# 0.net
KiCad netlist of a schematic drawn in Altium Designer
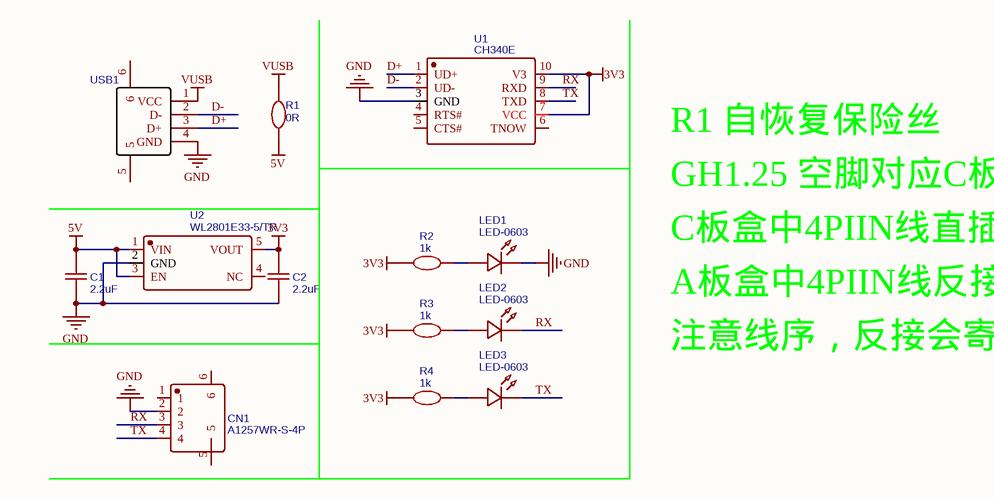
[diagram p0: 0.SchDoc]

(export (version "E")
  (design (tool "Eeschema 10.0.6"))
  (components
    (comp (ref "C1")
      (value "2.2uF")
      (footprint "C0603")
      (fields (field (name "CONTRIBUTOR") "LCEDA_Lib"))
      (libsource (lib "altium-import") (part "root_3_0.1u_"))
    )
    (comp (ref "C2")
      (value "2.2uF")
      (footprint "C0603")
      (fields (field (name "CONTRIBUTOR") "LCEDA_Lib"))
      (libsource (lib "altium-import") (part "root_3_0.1u_"))
    )
    (comp (ref "CN1")
      (value "A1257WR-S-4P")
      (footprint "CONN-SMD_A1257WR-S-4P")
      (fields (field (name "BOM_SUPPLIER PART") "C225127") (field (name "CONTRIBUTOR") "LCSC"))
      (libsource (lib "altium-import") (part "root_0_A1257WR-S-4P_"))
    )
    (comp (ref "LED1")
      (value "LED-0603")
      (footprint "LED0603_RED")
      (fields
        (field (name "BOM_MANUFACTURER PART") "19-217/R6C-AL1M2VY/3T")
        (field (name "BOM_SUPPLIER PART") "C72044")
        (field (name "CONTRIBUTOR") "LCEDA_01")
      )
      (libsource (lib "altium-import") (part "root_0_LED-0603_R_"))
    )
    (comp (ref "LED2")
      (value "LED-0603")
      (footprint "LED0603_RED")
      (fields
        (field (name "BOM_MANUFACTURER PART") "19-217/R6C-AL1M2VY/3T")
        (field (name "BOM_SUPPLIER PART") "C72044")
        (field (name "CONTRIBUTOR") "LCEDA_01")
      )
      (libsource (lib "altium-import") (part "root_0_LED-0603_R_"))
    )
    (comp (ref "LED3")
      (value "LED-0603")
      (footprint "LED0603_RED")
      (fields
        (field (name "BOM_MANUFACTURER PART") "19-217/R6C-AL1M2VY/3T")
        (field (name "BOM_SUPPLIER PART") "C72044")
        (field (name "CONTRIBUTOR") "LCEDA_01")
      )
      (libsource (lib "altium-import") (part "root_0_LED-0603_R_"))
    )
    (comp (ref "R1")
      (value "0R")
      (footprint "R0603")
      (fields (field (name "CONTRIBUTOR") "LCEDA_Lib"))
      (libsource (lib "altium-import") (part "root_3_1k_"))
    )
    (comp (ref "R2")
      (value "1k")
      (footprint "R0603")
      (fields (field (name "CONTRIBUTOR") "LCEDA_Lib"))
      (libsource (lib "altium-import") (part "root_0_1k_"))
    )
    (comp (ref "R3")
      (value "1k")
      (footprint "R0603")
      (fields (field (name "CONTRIBUTOR") "LCEDA_Lib"))
      (libsource (lib "altium-import") (part "root_0_1k_"))
    )
    (comp (ref "R4")
      (value "1k")
      (footprint "R0603")
      (fields (field (name "CONTRIBUTOR") "LCEDA_Lib"))
      (libsource (lib "altium-import") (part "root_0_1k_"))
    )
    (comp (ref "U1")
      (value "CH340E")
      (footprint "MSOP-10_L3.0-W3.0-P0.50-LS5.0-BL")
      (fields (field (name "BOM_SUPPLIER PART") "C99652"))
      (libsource (lib "altium-import") (part "root_0_CH340E_"))
    )
    (comp (ref "U2")
      (value "WL2801E33-5/TR")
      (footprint "SOT-23-5_L3.0-W1.7-P0.95-LS2.8-BR")
      (fields (field (name "BOM_SUPPLIER PART") "C167141") (field (name "CONTRIBUTOR") "LCSC"))
      (libsource (lib "altium-import") (part "root_0_WL2801E33-5/TR_"))
    )
    (comp (ref "USB1")
      (value "~")
      (footprint "USB-TH_U-G-04WS-W-04")
      (fields
        (field (name "BOM_SUPPLIER PART") "C879725")
        (field (name "BOM_MANUFACTURER PART") "U-G-04WS-W-04")
        (field (name "CONTRIBUTOR") "LCSC")
      )
      (libsource (lib "altium-import") (part "root_0_U-G-04WS-W-04_"))
    )
  )
  (nets
    (net (code "1") (name "/D+") (class "Default")
      (node (ref "U1") (pin "1") (pinfunction "UD+_1") (pintype "passive"))
      (node (ref "USB1") (pin "3") (pinfunction "D+_3") (pintype "passive"))
    )
    (net (code "2") (name "/D-") (class "Default")
      (node (ref "U1") (pin "2") (pinfunction "UD-_2") (pintype "passive"))
      (node (ref "USB1") (pin "2") (pinfunction "D-_2") (pintype "passive"))
    )
    (net (code "3") (name "/RX") (class "Default")
      (node (ref "CN1") (pin "3") (pinfunction "3_3") (pintype "passive"))
      (node (ref "LED2") (pin "2") (pinfunction "2_2") (pintype "passive"))
      (node (ref "U1") (pin "9") (pinfunction "RXD_9") (pintype "passive"))
    )
    (net (code "4") (name "/TX") (class "Default")
      (node (ref "CN1") (pin "4") (pinfunction "4_4") (pintype "passive"))
      (node (ref "LED3") (pin "2") (pinfunction "2_2") (pintype "passive"))
      (node (ref "U1") (pin "8") (pinfunction "TXD_8") (pintype "passive"))
    )
    (net (code "5") (name "3V3") (class "Default")
      (node (ref "C2") (pin "1") (pinfunction "1_1") (pintype "passive"))
      (node (ref "R2") (pin "1") (pinfunction "1_1") (pintype "passive"))
      (node (ref "R3") (pin "1") (pinfunction "1_1") (pintype "passive"))
      (node (ref "R4") (pin "1") (pinfunction "1_1") (pintype "passive"))
      (node (ref "U1") (pin "10") (pinfunction "V3_10") (pintype "passive"))
      (node (ref "U1") (pin "7") (pinfunction "VCC_7") (pintype "passive"))
      (node (ref "U2") (pin "5") (pinfunction "VOUT_5") (pintype "passive"))
    )
    (net (code "6") (name "5V") (class "Default")
      (node (ref "C1") (pin "1") (pinfunction "1_1") (pintype "passive"))
      (node (ref "R1") (pin "2") (pinfunction "2_2") (pintype "passive"))
      (node (ref "U2") (pin "1") (pinfunction "VIN_1") (pintype "passive"))
      (node (ref "U2") (pin "3") (pinfunction "EN_3") (pintype "passive"))
    )
    (net (code "7") (name "GND") (class "Default")
      (node (ref "C1") (pin "2") (pinfunction "2_2") (pintype "passive"))
      (node (ref "C2") (pin "2") (pinfunction "2_2") (pintype "passive"))
      (node (ref "CN1") (pin "2") (pinfunction "2_2") (pintype "passive"))
      (node (ref "LED1") (pin "2") (pinfunction "2_2") (pintype "passive"))
      (node (ref "U1") (pin "3") (pinfunction "GND_3") (pintype "passive"))
      (node (ref "U2") (pin "2") (pinfunction "GND_2") (pintype "passive"))
      (node (ref "USB1") (pin "4") (pinfunction "GND_4") (pintype "passive"))
    )
    (net (code "8") (name "Net-(LED1-Pad1)") (class "Default")
      (node (ref "LED1") (pin "1") (pinfunction "1_1") (pintype "passive"))
      (node (ref "R2") (pin "2") (pinfunction "2_2") (pintype "passive"))
    )
    (net (code "9") (name "Net-(LED2-Pad1)") (class "Default")
      (node (ref "LED2") (pin "1") (pinfunction "1_1") (pintype "passive"))
      (node (ref "R3") (pin "2") (pinfunction "2_2") (pintype "passive"))
    )
    (net (code "10") (name "Net-(LED3-Pad1)") (class "Default")
      (node (ref "LED3") (pin "1") (pinfunction "1_1") (pintype "passive"))
      (node (ref "R4") (pin "2") (pinfunction "2_2") (pintype "passive"))
    )
    (net (code "11") (name "VUSB") (class "Default")
      (node (ref "R1") (pin "1") (pinfunction "1_1") (pintype "passive"))
      (node (ref "USB1") (pin "1") (pinfunction "VCC_1") (pintype "passive"))
    )
    (net (code "12") (name "unconnected-(CN1-Pad1)") (class "Default")
      (node (ref "CN1") (pin "1") (pinfunction "1_1") (pintype "passive"))
    )
    (net (code "13") (name "unconnected-(CN1-Pad5)") (class "Default")
      (node (ref "CN1") (pin "5") (pinfunction "5_5") (pintype "passive"))
    )
    (net (code "14") (name "unconnected-(CN1-Pad6)") (class "Default")
      (node (ref "CN1") (pin "6") (pinfunction "6_6") (pintype "passive"))
    )
    (net (code "15") (name "unconnected-(U1-CTS#-Pad5)") (class "Default")
      (node (ref "U1") (pin "5") (pinfunction "CTS#_5") (pintype "passive"))
    )
    (net (code "16") (name "unconnected-(U1-RTS#-Pad4)") (class "Default")
      (node (ref "U1") (pin "4") (pinfunction "RTS#_4") (pintype "passive"))
    )
    (net (code "17") (name "unconnected-(U1-TNOW-Pad6)") (class "Default")
      (node (ref "U1") (pin "6") (pinfunction "TNOW_6") (pintype "passive"))
    )
    (net (code "18") (name "unconnected-(U2-NC-Pad4)") (class "Default")
      (node (ref "U2") (pin "4") (pinfunction "NC_4") (pintype "passive"))
    )
    (net (code "19") (name "unconnected-(USB1-Pad5)") (class "Default")
      (node (ref "USB1") (pin "5") (pinfunction "5_5") (pintype "passive"))
    )
    (net (code "20") (name "unconnected-(USB1-Pad6)") (class "Default")
      (node (ref "USB1") (pin "6") (pinfunction "6_6") (pintype "passive"))
    )
  )
)
